# Analog_Board.net
KiCad netlist of a schematic drawn in EAGLE
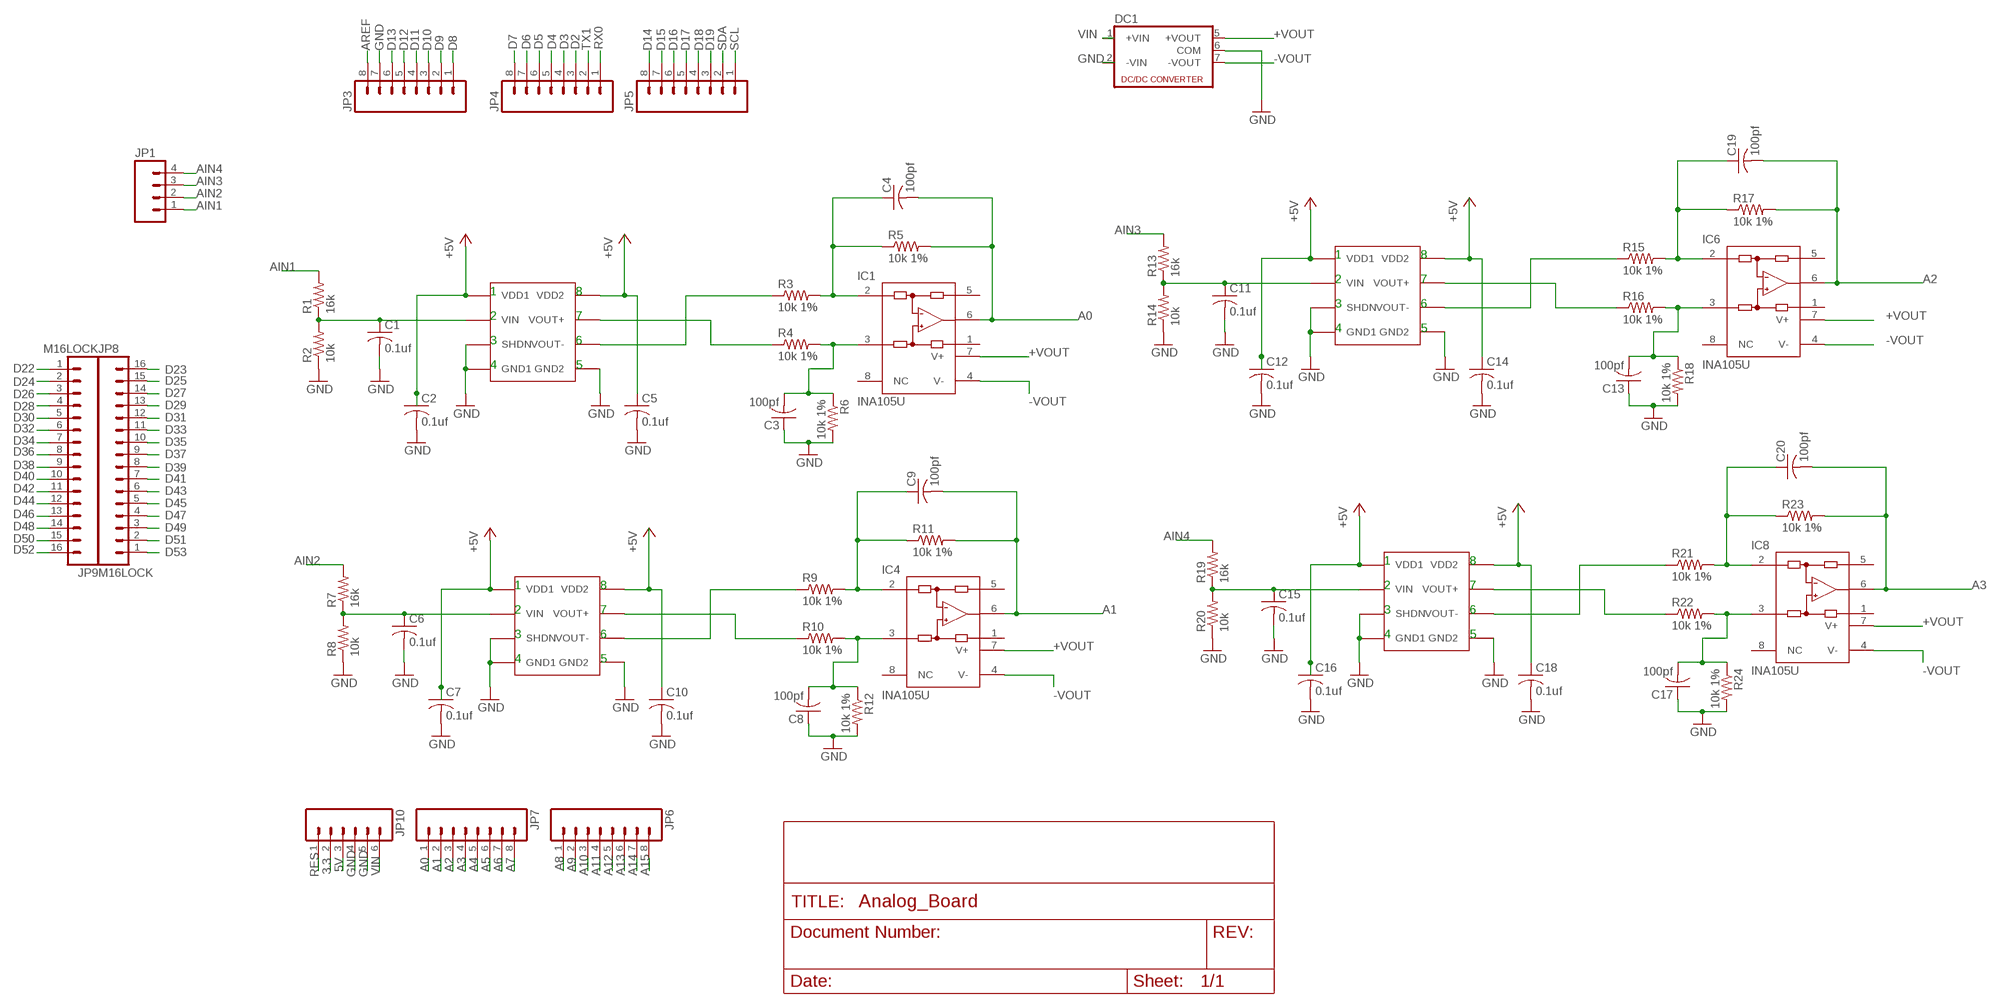
[diagram p0: schematic, sheet 1]

(export (version "E")
  (design (tool "Eeschema 10.0.6"))
  (components
    (comp (ref "C1")
      (value "0.1uf")
      (footprint "eagle-import:C0603")
      (libsource (lib "eagle-import") (part "C-USC0603"))
    )
    (comp (ref "C2")
      (value "0.1uf")
      (footprint "eagle-import:C0603")
      (libsource (lib "eagle-import") (part "C-USC0603"))
    )
    (comp (ref "C3")
      (value "100pf")
      (footprint "eagle-import:C0603")
      (libsource (lib "eagle-import") (part "C-USC0603"))
    )
    (comp (ref "C4")
      (value "100pf")
      (footprint "eagle-import:C0603")
      (libsource (lib "eagle-import") (part "C-USC0603"))
    )
    (comp (ref "C5")
      (value "0.1uf")
      (footprint "eagle-import:C0603")
      (libsource (lib "eagle-import") (part "C-USC0603"))
    )
    (comp (ref "C6")
      (value "0.1uf")
      (footprint "eagle-import:C0603")
      (libsource (lib "eagle-import") (part "C-USC0603"))
    )
    (comp (ref "C7")
      (value "0.1uf")
      (footprint "eagle-import:C0603")
      (libsource (lib "eagle-import") (part "C-USC0603"))
    )
    (comp (ref "C8")
      (value "100pf")
      (footprint "eagle-import:C0603")
      (libsource (lib "eagle-import") (part "C-USC0603"))
    )
    (comp (ref "C9")
      (value "100pf")
      (footprint "eagle-import:C0603")
      (libsource (lib "eagle-import") (part "C-USC0603"))
    )
    (comp (ref "C10")
      (value "0.1uf")
      (footprint "eagle-import:C0603")
      (libsource (lib "eagle-import") (part "C-USC0603"))
    )
    (comp (ref "C11")
      (value "0.1uf")
      (footprint "eagle-import:C0603")
      (libsource (lib "eagle-import") (part "C-USC0603"))
    )
    (comp (ref "C12")
      (value "0.1uf")
      (footprint "eagle-import:C0603")
      (libsource (lib "eagle-import") (part "C-USC0603"))
    )
    (comp (ref "C13")
      (value "100pf")
      (footprint "eagle-import:C0603")
      (libsource (lib "eagle-import") (part "C-USC0603"))
    )
    (comp (ref "C14")
      (value "0.1uf")
      (footprint "eagle-import:C0603")
      (libsource (lib "eagle-import") (part "C-USC0603"))
    )
    (comp (ref "C15")
      (value "0.1uf")
      (footprint "eagle-import:C0603")
      (libsource (lib "eagle-import") (part "C-USC0603"))
    )
    (comp (ref "C16")
      (value "0.1uf")
      (footprint "eagle-import:C0603")
      (libsource (lib "eagle-import") (part "C-USC0603"))
    )
    (comp (ref "C17")
      (value "100pf")
      (footprint "eagle-import:C0603")
      (libsource (lib "eagle-import") (part "C-USC0603"))
    )
    (comp (ref "C18")
      (value "0.1uf")
      (footprint "eagle-import:C0603")
      (libsource (lib "eagle-import") (part "C-USC0603"))
    )
    (comp (ref "C19")
      (value "100pf")
      (footprint "eagle-import:C0603")
      (libsource (lib "eagle-import") (part "C-USC0603"))
    )
    (comp (ref "C20")
      (value "100pf")
      (footprint "eagle-import:C0603")
      (libsource (lib "eagle-import") (part "C-USC0603"))
    )
    (comp (ref "DC1")
      (value "NMASIP8")
      (footprint "eagle-import:NMA")
      (libsource (lib "eagle-import") (part "NMASIP8"))
    )
    (comp (ref "IC1")
      (value "INA105U")
      (footprint "eagle-import:SO08")
      (fields (field (name "MF") "TEXAS INSTRUMENTS") (field (name "MPN") "INA105KU"))
      (libsource (lib "eagle-import") (part "INA105U"))
    )
    (comp (ref "IC2")
      (value "ACPL-C87A-000E")
      (footprint "eagle-import:SO8-WIDE")
      (libsource (lib "eagle-import") (part "ACPL-C87A-000E"))
    )
    (comp (ref "IC3")
      (value "ACPL-C87A-000E")
      (footprint "eagle-import:SO8-WIDE")
      (libsource (lib "eagle-import") (part "ACPL-C87A-000E"))
    )
    (comp (ref "IC4")
      (value "INA105U")
      (footprint "eagle-import:SO08")
      (fields (field (name "MF") "TEXAS INSTRUMENTS") (field (name "MPN") "INA105KU"))
      (libsource (lib "eagle-import") (part "INA105U"))
    )
    (comp (ref "IC5")
      (value "ACPL-C87A-000E")
      (footprint "eagle-import:SO8-WIDE")
      (libsource (lib "eagle-import") (part "ACPL-C87A-000E"))
    )
    (comp (ref "IC6")
      (value "INA105U")
      (footprint "eagle-import:SO08")
      (fields (field (name "MF") "TEXAS INSTRUMENTS") (field (name "MPN") "INA105KU"))
      (libsource (lib "eagle-import") (part "INA105U"))
    )
    (comp (ref "IC7")
      (value "ACPL-C87A-000E")
      (footprint "eagle-import:SO8-WIDE")
      (libsource (lib "eagle-import") (part "ACPL-C87A-000E"))
    )
    (comp (ref "IC8")
      (value "INA105U")
      (footprint "eagle-import:SO08")
      (fields (field (name "MF") "TEXAS INSTRUMENTS") (field (name "MPN") "INA105KU"))
      (libsource (lib "eagle-import") (part "INA105U"))
    )
    (comp (ref "JP1")
      (value "M04LOCK")
      (footprint "eagle-import:1X04_LOCK")
      (libsource (lib "eagle-import") (part "M04LOCK"))
    )
    (comp (ref "JP3")
      (value "M08LOCK")
      (footprint "eagle-import:1X08_LOCK")
      (libsource (lib "eagle-import") (part "M08LOCK"))
    )
    (comp (ref "JP4")
      (value "M08LOCK")
      (footprint "eagle-import:1X08_LOCK")
      (libsource (lib "eagle-import") (part "M08LOCK"))
    )
    (comp (ref "JP5")
      (value "M08LOCK")
      (footprint "eagle-import:1X08_LOCK")
      (libsource (lib "eagle-import") (part "M08LOCK"))
    )
    (comp (ref "JP6")
      (value "M08LOCK")
      (footprint "eagle-import:1X08_LOCK")
      (libsource (lib "eagle-import") (part "M08LOCK"))
    )
    (comp (ref "JP7")
      (value "M08LOCK")
      (footprint "eagle-import:1X08_LOCK")
      (libsource (lib "eagle-import") (part "M08LOCK"))
    )
    (comp (ref "JP8")
      (value "M16LOCK")
      (footprint "eagle-import:1X16_LOCK")
      (libsource (lib "eagle-import") (part "M16LOCK"))
    )
    (comp (ref "JP9")
      (value "M16LOCK")
      (footprint "eagle-import:1X16_LOCK")
      (libsource (lib "eagle-import") (part "M16LOCK"))
    )
    (comp (ref "JP10")
      (value "M06LOCK")
      (footprint "eagle-import:1X06_LOCK")
      (libsource (lib "eagle-import") (part "M06LOCK"))
    )
    (comp (ref "R1")
      (value "16k")
      (footprint "eagle-import:R0603")
      (libsource (lib "eagle-import") (part "R-US_R0603"))
    )
    (comp (ref "R2")
      (value "10k")
      (footprint "eagle-import:R0603")
      (libsource (lib "eagle-import") (part "R-US_R0603"))
    )
    (comp (ref "R3")
      (value "10k 1%")
      (footprint "eagle-import:R0603")
      (libsource (lib "eagle-import") (part "R-US_R0603"))
    )
    (comp (ref "R4")
      (value "10k 1%")
      (footprint "eagle-import:R0603")
      (libsource (lib "eagle-import") (part "R-US_R0603"))
    )
    (comp (ref "R5")
      (value "10k 1%")
      (footprint "eagle-import:R0603")
      (libsource (lib "eagle-import") (part "R-US_R0603"))
    )
    (comp (ref "R6")
      (value "10k 1%")
      (footprint "eagle-import:R0603")
      (libsource (lib "eagle-import") (part "R-US_R0603"))
    )
    (comp (ref "R7")
      (value "16k")
      (footprint "eagle-import:R0603")
      (libsource (lib "eagle-import") (part "R-US_R0603"))
    )
    (comp (ref "R8")
      (value "10k")
      (footprint "eagle-import:R0603")
      (libsource (lib "eagle-import") (part "R-US_R0603"))
    )
    (comp (ref "R9")
      (value "10k 1%")
      (footprint "eagle-import:R0603")
      (libsource (lib "eagle-import") (part "R-US_R0603"))
    )
    (comp (ref "R10")
      (value "10k 1%")
      (footprint "eagle-import:R0603")
      (libsource (lib "eagle-import") (part "R-US_R0603"))
    )
    (comp (ref "R11")
      (value "10k 1%")
      (footprint "eagle-import:R0603")
      (libsource (lib "eagle-import") (part "R-US_R0603"))
    )
    (comp (ref "R12")
      (value "10k 1%")
      (footprint "eagle-import:R0603")
      (libsource (lib "eagle-import") (part "R-US_R0603"))
    )
    (comp (ref "R13")
      (value "16k")
      (footprint "eagle-import:R0603")
      (libsource (lib "eagle-import") (part "R-US_R0603"))
    )
    (comp (ref "R14")
      (value "10k")
      (footprint "eagle-import:R0603")
      (libsource (lib "eagle-import") (part "R-US_R0603"))
    )
    (comp (ref "R15")
      (value "10k 1%")
      (footprint "eagle-import:R0603")
      (libsource (lib "eagle-import") (part "R-US_R0603"))
    )
    (comp (ref "R16")
      (value "10k 1%")
      (footprint "eagle-import:R0603")
      (libsource (lib "eagle-import") (part "R-US_R0603"))
    )
    (comp (ref "R17")
      (value "10k 1%")
      (footprint "eagle-import:R0603")
      (libsource (lib "eagle-import") (part "R-US_R0603"))
    )
    (comp (ref "R18")
      (value "10k 1%")
      (footprint "eagle-import:R0603")
      (libsource (lib "eagle-import") (part "R-US_R0603"))
    )
    (comp (ref "R19")
      (value "16k")
      (footprint "eagle-import:R0603")
      (libsource (lib "eagle-import") (part "R-US_R0603"))
    )
    (comp (ref "R20")
      (value "10k")
      (footprint "eagle-import:R0603")
      (libsource (lib "eagle-import") (part "R-US_R0603"))
    )
    (comp (ref "R21")
      (value "10k 1%")
      (footprint "eagle-import:R0603")
      (libsource (lib "eagle-import") (part "R-US_R0603"))
    )
    (comp (ref "R22")
      (value "10k 1%")
      (footprint "eagle-import:R0603")
      (libsource (lib "eagle-import") (part "R-US_R0603"))
    )
    (comp (ref "R23")
      (value "10k 1%")
      (footprint "eagle-import:R0603")
      (libsource (lib "eagle-import") (part "R-US_R0603"))
    )
    (comp (ref "R24")
      (value "10k 1%")
      (footprint "eagle-import:R0603")
      (libsource (lib "eagle-import") (part "R-US_R0603"))
    )
  )
  (nets
    (net (code "1") (name "+5V") (class "Default")
      (node (ref "C10") (pin "1") (pinfunction "1_1") (pintype "passive"))
      (node (ref "C12") (pin "1") (pinfunction "1_1") (pintype "passive"))
      (node (ref "C14") (pin "1") (pinfunction "1_1") (pintype "passive"))
      (node (ref "C16") (pin "1") (pinfunction "1_1") (pintype "passive"))
      (node (ref "C18") (pin "1") (pinfunction "1_1") (pintype "passive"))
      (node (ref "C2") (pin "1") (pinfunction "1_1") (pintype "passive"))
      (node (ref "C5") (pin "1") (pinfunction "1_1") (pintype "passive"))
      (node (ref "C7") (pin "1") (pinfunction "1_1") (pintype "passive"))
      (node (ref "IC2") (pin "1") (pinfunction "VDD1_1") (pintype "bidirectional"))
      (node (ref "IC2") (pin "8") (pinfunction "VDD2_8") (pintype "bidirectional"))
      (node (ref "IC3") (pin "1") (pinfunction "VDD1_1") (pintype "bidirectional"))
      (node (ref "IC3") (pin "8") (pinfunction "VDD2_8") (pintype "bidirectional"))
      (node (ref "IC5") (pin "1") (pinfunction "VDD1_1") (pintype "bidirectional"))
      (node (ref "IC5") (pin "8") (pinfunction "VDD2_8") (pintype "bidirectional"))
      (node (ref "IC7") (pin "1") (pinfunction "VDD1_1") (pintype "bidirectional"))
      (node (ref "IC7") (pin "8") (pinfunction "VDD2_8") (pintype "bidirectional"))
    )
    (net (code "2") (name "/+VOUT") (class "Default")
      (node (ref "DC1") (pin "5") (pinfunction "+VOUT_5") (pintype "passive"))
      (node (ref "IC1") (pin "7") (pinfunction "V+_7") (pintype "power_in"))
      (node (ref "IC4") (pin "7") (pinfunction "V+_7") (pintype "power_in"))
      (node (ref "IC6") (pin "7") (pinfunction "V+_7") (pintype "power_in"))
      (node (ref "IC8") (pin "7") (pinfunction "V+_7") (pintype "power_in"))
    )
    (net (code "3") (name "/-VOUT") (class "Default")
      (node (ref "DC1") (pin "7") (pinfunction "-VOUT_7") (pintype "passive"))
      (node (ref "IC1") (pin "4") (pinfunction "V-_4") (pintype "power_in"))
      (node (ref "IC4") (pin "4") (pinfunction "V-_4") (pintype "power_in"))
      (node (ref "IC6") (pin "4") (pinfunction "V-_4") (pintype "power_in"))
      (node (ref "IC8") (pin "4") (pinfunction "V-_4") (pintype "power_in"))
    )
    (net (code "4") (name "/3.3") (class "Default")
      (node (ref "JP10") (pin "2") (pinfunction "2_2") (pintype "passive"))
    )
    (net (code "5") (name "/5V") (class "Default")
      (node (ref "JP10") (pin "3") (pinfunction "3_3") (pintype "passive"))
    )
    (net (code "6") (name "/A0") (class "Default")
      (node (ref "C4") (pin "2") (pinfunction "2_2") (pintype "passive"))
      (node (ref "IC1") (pin "6") (pinfunction "OUT_6") (pintype "output"))
      (node (ref "JP7") (pin "1") (pinfunction "1_1") (pintype "passive"))
      (node (ref "R5") (pin "2") (pinfunction "2_2") (pintype "passive"))
    )
    (net (code "7") (name "/A1") (class "Default")
      (node (ref "C9") (pin "2") (pinfunction "2_2") (pintype "passive"))
      (node (ref "IC4") (pin "6") (pinfunction "OUT_6") (pintype "output"))
      (node (ref "JP7") (pin "2") (pinfunction "2_2") (pintype "passive"))
      (node (ref "R11") (pin "2") (pinfunction "2_2") (pintype "passive"))
    )
    (net (code "8") (name "/A2") (class "Default")
      (node (ref "C19") (pin "2") (pinfunction "2_2") (pintype "passive"))
      (node (ref "IC6") (pin "6") (pinfunction "OUT_6") (pintype "output"))
      (node (ref "JP7") (pin "3") (pinfunction "3_3") (pintype "passive"))
      (node (ref "R17") (pin "2") (pinfunction "2_2") (pintype "passive"))
    )
    (net (code "9") (name "/A3") (class "Default")
      (node (ref "C20") (pin "2") (pinfunction "2_2") (pintype "passive"))
      (node (ref "IC8") (pin "6") (pinfunction "OUT_6") (pintype "output"))
      (node (ref "JP7") (pin "4") (pinfunction "4_4") (pintype "passive"))
      (node (ref "R23") (pin "2") (pinfunction "2_2") (pintype "passive"))
    )
    (net (code "10") (name "/A4") (class "Default")
      (node (ref "JP7") (pin "5") (pinfunction "5_5") (pintype "passive"))
    )
    (net (code "11") (name "/A5") (class "Default")
      (node (ref "JP7") (pin "6") (pinfunction "6_6") (pintype "passive"))
    )
    (net (code "12") (name "/A6") (class "Default")
      (node (ref "JP7") (pin "7") (pinfunction "7_7") (pintype "passive"))
    )
    (net (code "13") (name "/A7") (class "Default")
      (node (ref "JP7") (pin "8") (pinfunction "8_8") (pintype "passive"))
    )
    (net (code "14") (name "/A8") (class "Default")
      (node (ref "JP6") (pin "1") (pinfunction "1_1") (pintype "passive"))
    )
    (net (code "15") (name "/A9") (class "Default")
      (node (ref "JP6") (pin "2") (pinfunction "2_2") (pintype "passive"))
    )
    (net (code "16") (name "/A10") (class "Default")
      (node (ref "JP6") (pin "3") (pinfunction "3_3") (pintype "passive"))
    )
    (net (code "17") (name "/A11") (class "Default")
      (node (ref "JP6") (pin "4") (pinfunction "4_4") (pintype "passive"))
    )
    (net (code "18") (name "/A12") (class "Default")
      (node (ref "JP6") (pin "5") (pinfunction "5_5") (pintype "passive"))
    )
    (net (code "19") (name "/A13") (class "Default")
      (node (ref "JP6") (pin "6") (pinfunction "6_6") (pintype "passive"))
    )
    (net (code "20") (name "/A14") (class "Default")
      (node (ref "JP6") (pin "7") (pinfunction "7_7") (pintype "passive"))
    )
    (net (code "21") (name "/A15") (class "Default")
      (node (ref "JP6") (pin "8") (pinfunction "8_8") (pintype "passive"))
    )
    (net (code "22") (name "/AIN1") (class "Default")
      (node (ref "JP1") (pin "1") (pinfunction "1_1") (pintype "passive"))
      (node (ref "R1") (pin "2") (pinfunction "2_2") (pintype "passive"))
    )
    (net (code "23") (name "/AIN2") (class "Default")
      (node (ref "JP1") (pin "2") (pinfunction "2_2") (pintype "passive"))
      (node (ref "R7") (pin "2") (pinfunction "2_2") (pintype "passive"))
    )
    (net (code "24") (name "/AIN3") (class "Default")
      (node (ref "JP1") (pin "3") (pinfunction "3_3") (pintype "passive"))
      (node (ref "R13") (pin "2") (pinfunction "2_2") (pintype "passive"))
    )
    (net (code "25") (name "/AIN4") (class "Default")
      (node (ref "JP1") (pin "4") (pinfunction "4_4") (pintype "passive"))
      (node (ref "R19") (pin "2") (pinfunction "2_2") (pintype "passive"))
    )
    (net (code "26") (name "/AREF") (class "Default")
      (node (ref "JP3") (pin "8") (pinfunction "8_8") (pintype "passive"))
    )
    (net (code "27") (name "/D2") (class "Default")
      (node (ref "JP4") (pin "3") (pinfunction "3_3") (pintype "passive"))
    )
    (net (code "28") (name "/D3") (class "Default")
      (node (ref "JP4") (pin "4") (pinfunction "4_4") (pintype "passive"))
    )
    (net (code "29") (name "/D4") (class "Default")
      (node (ref "JP4") (pin "5") (pinfunction "5_5") (pintype "passive"))
    )
    (net (code "30") (name "/D5") (class "Default")
      (node (ref "JP4") (pin "6") (pinfunction "6_6") (pintype "passive"))
    )
    (net (code "31") (name "/D6") (class "Default")
      (node (ref "JP4") (pin "7") (pinfunction "7_7") (pintype "passive"))
    )
    (net (code "32") (name "/D7") (class "Default")
      (node (ref "JP4") (pin "8") (pinfunction "8_8") (pintype "passive"))
    )
    (net (code "33") (name "/D8") (class "Default")
      (node (ref "JP3") (pin "1") (pinfunction "1_1") (pintype "passive"))
    )
    (net (code "34") (name "/D9") (class "Default")
      (node (ref "JP3") (pin "2") (pinfunction "2_2") (pintype "passive"))
    )
    (net (code "35") (name "/D10") (class "Default")
      (node (ref "JP3") (pin "3") (pinfunction "3_3") (pintype "passive"))
    )
    (net (code "36") (name "/D11") (class "Default")
      (node (ref "JP3") (pin "4") (pinfunction "4_4") (pintype "passive"))
    )
    (net (code "37") (name "/D12") (class "Default")
      (node (ref "JP3") (pin "5") (pinfunction "5_5") (pintype "passive"))
    )
    (net (code "38") (name "/D13") (class "Default")
      (node (ref "JP3") (pin "6") (pinfunction "6_6") (pintype "passive"))
    )
    (net (code "39") (name "/D14") (class "Default")
      (node (ref "JP5") (pin "8") (pinfunction "8_8") (pintype "passive"))
    )
    (net (code "40") (name "/D15") (class "Default")
      (node (ref "JP5") (pin "7") (pinfunction "7_7") (pintype "passive"))
    )
    (net (code "41") (name "/D16") (class "Default")
      (node (ref "JP5") (pin "6") (pinfunction "6_6") (pintype "passive"))
    )
    (net (code "42") (name "/D17") (class "Default")
      (node (ref "JP5") (pin "5") (pinfunction "5_5") (pintype "passive"))
    )
    (net (code "43") (name "/D18") (class "Default")
      (node (ref "JP5") (pin "4") (pinfunction "4_4") (pintype "passive"))
    )
    (net (code "44") (name "/D19") (class "Default")
      (node (ref "JP5") (pin "3") (pinfunction "3_3") (pintype "passive"))
    )
    (net (code "45") (name "/D22") (class "Default")
      (node (ref "JP9") (pin "1") (pinfunction "1_1") (pintype "passive"))
    )
    (net (code "46") (name "/D23") (class "Default")
      (node (ref "JP8") (pin "16") (pinfunction "16_16") (pintype "passive"))
    )
    (net (code "47") (name "/D24") (class "Default")
      (node (ref "JP9") (pin "2") (pinfunction "2_2") (pintype "passive"))
    )
    (net (code "48") (name "/D25") (class "Default")
      (node (ref "JP8") (pin "15") (pinfunction "15_15") (pintype "passive"))
    )
    (net (code "49") (name "/D26") (class "Default")
      (node (ref "JP9") (pin "3") (pinfunction "3_3") (pintype "passive"))
    )
    (net (code "50") (name "/D27") (class "Default")
      (node (ref "JP8") (pin "14") (pinfunction "14_14") (pintype "passive"))
    )
    (net (code "51") (name "/D28") (class "Default")
      (node (ref "JP9") (pin "4") (pinfunction "4_4") (pintype "passive"))
    )
    (net (code "52") (name "/D29") (class "Default")
      (node (ref "JP8") (pin "13") (pinfunction "13_13") (pintype "passive"))
    )
    (net (code "53") (name "/D30") (class "Default")
      (node (ref "JP9") (pin "5") (pinfunction "5_5") (pintype "passive"))
    )
    (net (code "54") (name "/D31") (class "Default")
      (node (ref "JP8") (pin "12") (pinfunction "12_12") (pintype "passive"))
    )
    (net (code "55") (name "/D32") (class "Default")
      (node (ref "JP9") (pin "6") (pinfunction "6_6") (pintype "passive"))
    )
    (net (code "56") (name "/D33") (class "Default")
      (node (ref "JP8") (pin "11") (pinfunction "11_11") (pintype "passive"))
    )
    (net (code "57") (name "/D34") (class "Default")
      (node (ref "JP9") (pin "7") (pinfunction "7_7") (pintype "passive"))
    )
    (net (code "58") (name "/D35") (class "Default")
      (node (ref "JP8") (pin "10") (pinfunction "10_10") (pintype "passive"))
    )
    (net (code "59") (name "/D36") (class "Default")
      (node (ref "JP9") (pin "8") (pinfunction "8_8") (pintype "passive"))
    )
    (net (code "60") (name "/D37") (class "Default")
      (node (ref "JP8") (pin "9") (pinfunction "9_9") (pintype "passive"))
    )
    (net (code "61") (name "/D38") (class "Default")
      (node (ref "JP9") (pin "9") (pinfunction "9_9") (pintype "passive"))
    )
    (net (code "62") (name "/D39") (class "Default")
      (node (ref "JP8") (pin "8") (pinfunction "8_8") (pintype "passive"))
    )
    (net (code "63") (name "/D40") (class "Default")
      (node (ref "JP9") (pin "10") (pinfunction "10_10") (pintype "passive"))
    )
    (net (code "64") (name "/D41") (class "Default")
      (node (ref "JP8") (pin "7") (pinfunction "7_7") (pintype "passive"))
    )
    (net (code "65") (name "/D42") (class "Default")
      (node (ref "JP9") (pin "11") (pinfunction "11_11") (pintype "passive"))
    )
    (net (code "66") (name "/D43") (class "Default")
      (node (ref "JP8") (pin "6") (pinfunction "6_6") (pintype "passive"))
    )
    (net (code "67") (name "/D44") (class "Default")
      (node (ref "JP9") (pin "12") (pinfunction "12_12") (pintype "passive"))
    )
    (net (code "68") (name "/D45") (class "Default")
      (node (ref "JP8") (pin "5") (pinfunction "5_5") (pintype "passive"))
    )
    (net (code "69") (name "/D46") (class "Default")
      (node (ref "JP9") (pin "13") (pinfunction "13_13") (pintype "passive"))
    )
    (net (code "70") (name "/D47") (class "Default")
      (node (ref "JP8") (pin "4") (pinfunction "4_4") (pintype "passive"))
    )
    (net (code "71") (name "/D48") (class "Default")
      (node (ref "JP9") (pin "14") (pinfunction "14_14") (pintype "passive"))
    )
    (net (code "72") (name "/D49") (class "Default")
      (node (ref "JP8") (pin "3") (pinfunction "3_3") (pintype "passive"))
    )
    (net (code "73") (name "/D50") (class "Default")
      (node (ref "JP9") (pin "15") (pinfunction "15_15") (pintype "passive"))
    )
    (net (code "74") (name "/D51") (class "Default")
      (node (ref "JP8") (pin "2") (pinfunction "2_2") (pintype "passive"))
    )
    (net (code "75") (name "/D52") (class "Default")
      (node (ref "JP9") (pin "16") (pinfunction "16_16") (pintype "passive"))
    )
    (net (code "76") (name "/D53") (class "Default")
      (node (ref "JP8") (pin "1") (pinfunction "1_1") (pintype "passive"))
    )
    (net (code "77") (name "/RES") (class "Default")
      (node (ref "JP10") (pin "1") (pinfunction "1_1") (pintype "passive"))
    )
    (net (code "78") (name "/RX0") (class "Default")
      (node (ref "JP4") (pin "1") (pinfunction "1_1") (pintype "passive"))
    )
    (net (code "79") (name "/SCL") (class "Default")
      (node (ref "JP5") (pin "1") (pinfunction "1_1") (pintype "passive"))
    )
    (net (code "80") (name "/SDA") (class "Default")
      (node (ref "JP5") (pin "2") (pinfunction "2_2") (pintype "passive"))
    )
    (net (code "81") (name "/TX1") (class "Default")
      (node (ref "JP4") (pin "2") (pinfunction "2_2") (pintype "passive"))
    )
    (net (code "82") (name "/VIN") (class "Default")
      (node (ref "DC1") (pin "1") (pinfunction "+VIN_1") (pintype "passive"))
      (node (ref "JP10") (pin "6") (pinfunction "6_6") (pintype "passive"))
    )
    (net (code "83") (name "GND") (class "Default")
      (node (ref "C1") (pin "2") (pinfunction "2_2") (pintype "passive"))
      (node (ref "C10") (pin "2") (pinfunction "2_2") (pintype "passive"))
      (node (ref "C11") (pin "2") (pinfunction "2_2") (pintype "passive"))
      (node (ref "C12") (pin "2") (pinfunction "2_2") (pintype "passive"))
      (node (ref "C13") (pin "1") (pinfunction "1_1") (pintype "passive"))
      (node (ref "C14") (pin "2") (pinfunction "2_2") (pintype "passive"))
      (node (ref "C15") (pin "2") (pinfunction "2_2") (pintype "passive"))
      (node (ref "C16") (pin "2") (pinfunction "2_2") (pintype "passive"))
      (node (ref "C17") (pin "1") (pinfunction "1_1") (pintype "passive"))
      (node (ref "C18") (pin "2") (pinfunction "2_2") (pintype "passive"))
      (node (ref "C2") (pin "2") (pinfunction "2_2") (pintype "passive"))
      (node (ref "C3") (pin "1") (pinfunction "1_1") (pintype "passive"))
      (node (ref "C5") (pin "2") (pinfunction "2_2") (pintype "passive"))
      (node (ref "C6") (pin "2") (pinfunction "2_2") (pintype "passive"))
      (node (ref "C7") (pin "2") (pinfunction "2_2") (pintype "passive"))
      (node (ref "C8") (pin "1") (pinfunction "1_1") (pintype "passive"))
      (node (ref "DC1") (pin "2") (pinfunction "-VIN_2") (pintype "passive"))
      (node (ref "DC1") (pin "6") (pinfunction "COM_6") (pintype "passive"))
      (node (ref "IC2") (pin "3") (pinfunction "SHDN_3") (pintype "bidirectional"))
      (node (ref "IC2") (pin "4") (pinfunction "GND1_4") (pintype "bidirectional"))
      (node (ref "IC2") (pin "5") (pinfunction "GND2_5") (pintype "bidirectional"))
      (node (ref "IC3") (pin "3") (pinfunction "SHDN_3") (pintype "bidirectional"))
      (node (ref "IC3") (pin "4") (pinfunction "GND1_4") (pintype "bidirectional"))
      (node (ref "IC3") (pin "5") (pinfunction "GND2_5") (pintype "bidirectional"))
      (node (ref "IC5") (pin "3") (pinfunction "SHDN_3") (pintype "bidirectional"))
      (node (ref "IC5") (pin "4") (pinfunction "GND1_4") (pintype "bidirectional"))
      (node (ref "IC5") (pin "5") (pinfunction "GND2_5") (pintype "bidirectional"))
      (node (ref "IC7") (pin "3") (pinfunction "SHDN_3") (pintype "bidirectional"))
      (node (ref "IC7") (pin "4") (pinfunction "GND1_4") (pintype "bidirectional"))
      (node (ref "IC7") (pin "5") (pinfunction "GND2_5") (pintype "bidirectional"))
      (node (ref "JP10") (pin "4") (pinfunction "4_4") (pintype "passive"))
      (node (ref "JP10") (pin "5") (pinfunction "5_5") (pintype "passive"))
      (node (ref "JP3") (pin "7") (pinfunction "7_7") (pintype "passive"))
      (node (ref "R12") (pin "2") (pinfunction "2_2") (pintype "passive"))
      (node (ref "R14") (pin "1") (pinfunction "1_1") (pintype "passive"))
      (node (ref "R18") (pin "2") (pinfunction "2_2") (pintype "passive"))
      (node (ref "R2") (pin "1") (pinfunction "1_1") (pintype "passive"))
      (node (ref "R20") (pin "1") (pinfunction "1_1") (pintype "passive"))
      (node (ref "R24") (pin "2") (pinfunction "2_2") (pintype "passive"))
      (node (ref "R6") (pin "2") (pinfunction "2_2") (pintype "passive"))
      (node (ref "R8") (pin "1") (pinfunction "1_1") (pintype "passive"))
    )
    (net (code "84") (name "Net-(IC1-+IN)") (class "Default")
      (node (ref "C3") (pin "2") (pinfunction "2_2") (pintype "passive"))
      (node (ref "IC1") (pin "3") (pinfunction "+IN_3") (pintype "input"))
      (node (ref "R4") (pin "2") (pinfunction "2_2") (pintype "passive"))
      (node (ref "R6") (pin "1") (pinfunction "1_1") (pintype "passive"))
    )
    (net (code "85") (name "Net-(IC1--IN)") (class "Default")
      (node (ref "C4") (pin "1") (pinfunction "1_1") (pintype "passive"))
      (node (ref "IC1") (pin "2") (pinfunction "-IN_2") (pintype "input"))
      (node (ref "R3") (pin "2") (pinfunction "2_2") (pintype "passive"))
      (node (ref "R5") (pin "1") (pinfunction "1_1") (pintype "passive"))
    )
    (net (code "86") (name "Net-(IC2-VIN)") (class "Default")
      (node (ref "C1") (pin "1") (pinfunction "1_1") (pintype "passive"))
      (node (ref "IC2") (pin "2") (pinfunction "VIN_2") (pintype "bidirectional"))
      (node (ref "R1") (pin "1") (pinfunction "1_1") (pintype "passive"))
      (node (ref "R2") (pin "2") (pinfunction "2_2") (pintype "passive"))
    )
    (net (code "87") (name "Net-(IC2-VOUT+)") (class "Default")
      (node (ref "IC2") (pin "7") (pinfunction "VOUT+_7") (pintype "bidirectional"))
      (node (ref "R4") (pin "1") (pinfunction "1_1") (pintype "passive"))
    )
    (net (code "88") (name "Net-(IC2-VOUT-)") (class "Default")
      (node (ref "IC2") (pin "6") (pinfunction "VOUT-_6") (pintype "bidirectional"))
      (node (ref "R3") (pin "1") (pinfunction "1_1") (pintype "passive"))
    )
    (net (code "89") (name "Net-(IC3-VIN)") (class "Default")
      (node (ref "C6") (pin "1") (pinfunction "1_1") (pintype "passive"))
      (node (ref "IC3") (pin "2") (pinfunction "VIN_2") (pintype "bidirectional"))
      (node (ref "R7") (pin "1") (pinfunction "1_1") (pintype "passive"))
      (node (ref "R8") (pin "2") (pinfunction "2_2") (pintype "passive"))
    )
    (net (code "90") (name "Net-(IC3-VOUT+)") (class "Default")
      (node (ref "IC3") (pin "7") (pinfunction "VOUT+_7") (pintype "bidirectional"))
      (node (ref "R10") (pin "1") (pinfunction "1_1") (pintype "passive"))
    )
    (net (code "91") (name "Net-(IC3-VOUT-)") (class "Default")
      (node (ref "IC3") (pin "6") (pinfunction "VOUT-_6") (pintype "bidirectional"))
      (node (ref "R9") (pin "1") (pinfunction "1_1") (pintype "passive"))
    )
    (net (code "92") (name "Net-(IC4-+IN)") (class "Default")
      (node (ref "C8") (pin "2") (pinfunction "2_2") (pintype "passive"))
      (node (ref "IC4") (pin "3") (pinfunction "+IN_3") (pintype "input"))
      (node (ref "R10") (pin "2") (pinfunction "2_2") (pintype "passive"))
      (node (ref "R12") (pin "1") (pinfunction "1_1") (pintype "passive"))
    )
    (net (code "93") (name "Net-(IC4--IN)") (class "Default")
      (node (ref "C9") (pin "1") (pinfunction "1_1") (pintype "passive"))
      (node (ref "IC4") (pin "2") (pinfunction "-IN_2") (pintype "input"))
      (node (ref "R11") (pin "1") (pinfunction "1_1") (pintype "passive"))
      (node (ref "R9") (pin "2") (pinfunction "2_2") (pintype "passive"))
    )
    (net (code "94") (name "Net-(IC5-VIN)") (class "Default")
      (node (ref "C11") (pin "1") (pinfunction "1_1") (pintype "passive"))
      (node (ref "IC5") (pin "2") (pinfunction "VIN_2") (pintype "bidirectional"))
      (node (ref "R13") (pin "1") (pinfunction "1_1") (pintype "passive"))
      (node (ref "R14") (pin "2") (pinfunction "2_2") (pintype "passive"))
    )
    (net (code "95") (name "Net-(IC5-VOUT+)") (class "Default")
      (node (ref "IC5") (pin "7") (pinfunction "VOUT+_7") (pintype "bidirectional"))
      (node (ref "R16") (pin "1") (pinfunction "1_1") (pintype "passive"))
    )
    (net (code "96") (name "Net-(IC5-VOUT-)") (class "Default")
      (node (ref "IC5") (pin "6") (pinfunction "VOUT-_6") (pintype "bidirectional"))
      (node (ref "R15") (pin "1") (pinfunction "1_1") (pintype "passive"))
    )
    (net (code "97") (name "Net-(IC6-+IN)") (class "Default")
      (node (ref "C13") (pin "2") (pinfunction "2_2") (pintype "passive"))
      (node (ref "IC6") (pin "3") (pinfunction "+IN_3") (pintype "input"))
      (node (ref "R16") (pin "2") (pinfunction "2_2") (pintype "passive"))
      (node (ref "R18") (pin "1") (pinfunction "1_1") (pintype "passive"))
    )
    (net (code "98") (name "Net-(IC6--IN)") (class "Default")
      (node (ref "C19") (pin "1") (pinfunction "1_1") (pintype "passive"))
      (node (ref "IC6") (pin "2") (pinfunction "-IN_2") (pintype "input"))
      (node (ref "R15") (pin "2") (pinfunction "2_2") (pintype "passive"))
      (node (ref "R17") (pin "1") (pinfunction "1_1") (pintype "passive"))
    )
    (net (code "99") (name "Net-(IC7-VIN)") (class "Default")
      (node (ref "C15") (pin "1") (pinfunction "1_1") (pintype "passive"))
      (node (ref "IC7") (pin "2") (pinfunction "VIN_2") (pintype "bidirectional"))
      (node (ref "R19") (pin "1") (pinfunction "1_1") (pintype "passive"))
      (node (ref "R20") (pin "2") (pinfunction "2_2") (pintype "passive"))
    )
    (net (code "100") (name "Net-(IC7-VOUT+)") (class "Default")
      (node (ref "IC7") (pin "7") (pinfunction "VOUT+_7") (pintype "bidirectional"))
      (node (ref "R22") (pin "1") (pinfunction "1_1") (pintype "passive"))
    )
    (net (code "101") (name "Net-(IC7-VOUT-)") (class "Default")
      (node (ref "IC7") (pin "6") (pinfunction "VOUT-_6") (pintype "bidirectional"))
      (node (ref "R21") (pin "1") (pinfunction "1_1") (pintype "passive"))
    )
    (net (code "102") (name "Net-(IC8-+IN)") (class "Default")
      (node (ref "C17") (pin "2") (pinfunction "2_2") (pintype "passive"))
      (node (ref "IC8") (pin "3") (pinfunction "+IN_3") (pintype "input"))
      (node (ref "R22") (pin "2") (pinfunction "2_2") (pintype "passive"))
      (node (ref "R24") (pin "1") (pinfunction "1_1") (pintype "passive"))
    )
    (net (code "103") (name "Net-(IC8--IN)") (class "Default")
      (node (ref "C20") (pin "1") (pinfunction "1_1") (pintype "passive"))
      (node (ref "IC8") (pin "2") (pinfunction "-IN_2") (pintype "input"))
      (node (ref "R21") (pin "2") (pinfunction "2_2") (pintype "passive"))
      (node (ref "R23") (pin "1") (pinfunction "1_1") (pintype "passive"))
    )
    (net (code "104") (name "unconnected-(IC1-NC-Pad8)") (class "Default")
      (node (ref "IC1") (pin "8") (pinfunction "NC_8") (pintype "no_connect"))
    )
    (net (code "105") (name "unconnected-(IC1-REF-Pad1)") (class "Default")
      (node (ref "IC1") (pin "1") (pinfunction "REF_1") (pintype "passive"))
    )
    (net (code "106") (name "unconnected-(IC1-SENSE-Pad5)") (class "Default")
      (node (ref "IC1") (pin "5") (pinfunction "SENSE_5") (pintype "passive"))
    )
    (net (code "107") (name "unconnected-(IC4-NC-Pad8)") (class "Default")
      (node (ref "IC4") (pin "8") (pinfunction "NC_8") (pintype "no_connect"))
    )
    (net (code "108") (name "unconnected-(IC4-REF-Pad1)") (class "Default")
      (node (ref "IC4") (pin "1") (pinfunction "REF_1") (pintype "passive"))
    )
    (net (code "109") (name "unconnected-(IC4-SENSE-Pad5)") (class "Default")
      (node (ref "IC4") (pin "5") (pinfunction "SENSE_5") (pintype "passive"))
    )
    (net (code "110") (name "unconnected-(IC6-NC-Pad8)") (class "Default")
      (node (ref "IC6") (pin "8") (pinfunction "NC_8") (pintype "no_connect"))
    )
    (net (code "111") (name "unconnected-(IC6-REF-Pad1)") (class "Default")
      (node (ref "IC6") (pin "1") (pinfunction "REF_1") (pintype "passive"))
    )
    (net (code "112") (name "unconnected-(IC6-SENSE-Pad5)") (class "Default")
      (node (ref "IC6") (pin "5") (pinfunction "SENSE_5") (pintype "passive"))
    )
    (net (code "113") (name "unconnected-(IC8-NC-Pad8)") (class "Default")
      (node (ref "IC8") (pin "8") (pinfunction "NC_8") (pintype "no_connect"))
    )
    (net (code "114") (name "unconnected-(IC8-REF-Pad1)") (class "Default")
      (node (ref "IC8") (pin "1") (pinfunction "REF_1") (pintype "passive"))
    )
    (net (code "115") (name "unconnected-(IC8-SENSE-Pad5)") (class "Default")
      (node (ref "IC8") (pin "5") (pinfunction "SENSE_5") (pintype "passive"))
    )
  )
)
